# switching.net
KiCad netlist of a schematic drawn in Altium Designer
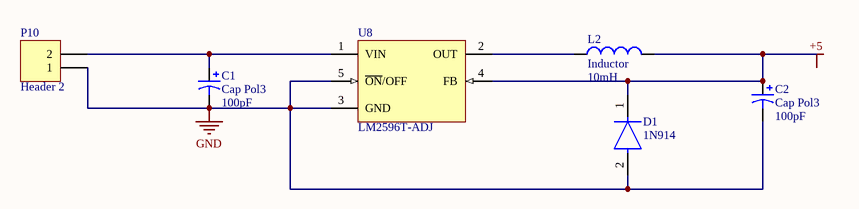
[diagram p0: switching.SchDoc]

(export (version "E")
  (design (tool "Eeschema 10.0.6"))
  (components
    (comp (ref "C1")
      (value "Cap Pol3")
      (footprint "C0805")
      (description "Polarized Capacitor (Surface Mount)")
      (fields (field (name "ALTIUM_VALUE") "100pF") (field (name "PUBLISHER") "Altium Limited"))
      (libsource (lib "Miscellaneous Devices") (part "Cap Pol3"))
    )
    (comp (ref "C2")
      (value "Cap Pol3")
      (footprint "C0805")
      (description "Polarized Capacitor (Surface Mount)")
      (fields (field (name "ALTIUM_VALUE") "100pF") (field (name "PUBLISHER") "Altium Limited"))
      (libsource (lib "Miscellaneous Devices") (part "Cap Pol3"))
    )
    (comp (ref "D1")
      (value "1N914")
      (footprint "FP-502-01-MFG")
      (description "DIODE GEN PURP 75V 200MA SOD523F")
      (fields
        (field (name "MANUFACTURER PART NUMBER") "1N914BWT")
        (field (name "OCTOPART") "https://octopart.com/1n914bwt-on+semiconductor-84323166")
      )
      (libsource (lib "Altium Content Vault") (part "d7152d700b627762746794eb795d46e"))
    )
    (comp (ref "L2")
      (value "Inductor")
      (footprint "0402-A")
      (fields (field (name "ALTIUM_VALUE") "10mH") (field (name "PUBLISHER") "Altium Limited"))
      (libsource (lib "Miscellaneous Devices") (part "Inductor"))
    )
    (comp (ref "P10")
      (value "Header 2")
      (footprint "HDR1X2")
      (description "Header, 2-Pin")
      (fields (field (name "PUBLISHER") "Altium Limited"))
      (libsource (lib "Miscellaneous Connectors") (part "Header 2"))
    )
    (comp (ref "U8")
      (value "LM2596T-ADJ")
      (footprint "NDH0005A")
      (description "SIMPLE SWITCHER® Power Converter 150 KHz 3A Step-Down Voltage Regulator, 5-pin TO-220")
      (fields (field (name "MANUFACTURER") "Texas Instruments"))
      (libsource (lib "Altium Content Vault") (part "PM-REG-LM2575HVT-12"))
    )
  )
  (nets
    (net (code "2") (name "GND") (class "Default")
      (node (ref "C1") (pin "2") (pinfunction "2_2") (pintype "passive"))
      (node (ref "C2") (pin "2") (pinfunction "2_2") (pintype "passive"))
      (node (ref "D1") (pin "2") (pinfunction "A_2") (pintype "passive"))
      (node (ref "P10") (pin "1") (pinfunction "1_1") (pintype "passive"))
      (node (ref "U8") (pin "3") (pinfunction "GND_3") (pintype "power_in"))
      (node (ref "U8") (pin "5") (pinfunction "~{ON}/OFF_5") (pintype "input"))
    )
    (net (code "3") (name "Net-(D1-C)") (class "Default")
      (node (ref "C2") (pin "1") (pinfunction "1_1") (pintype "passive"))
      (node (ref "D1") (pin "1") (pinfunction "C_1") (pintype "passive"))
      (node (ref "L2") (pin "2") (pinfunction "2_2") (pintype "passive"))
      (node (ref "U8") (pin "4") (pinfunction "FB_4") (pintype "input"))
    )
    (net (code "4") (name "Net-(U8-OUT)") (class "Default")
      (node (ref "L2") (pin "1") (pinfunction "1_1") (pintype "passive"))
      (node (ref "U8") (pin "2") (pinfunction "OUT_2") (pintype "power_in"))
    )
    (net (code "5") (name "Net-(U8-VIN)") (class "Default")
      (node (ref "C1") (pin "1") (pinfunction "1_1") (pintype "passive"))
      (node (ref "P10") (pin "2") (pinfunction "2_2") (pintype "passive"))
      (node (ref "U8") (pin "1") (pinfunction "VIN_1") (pintype "power_in"))
    )
  )
)
